# Power.net
KiCad netlist of a schematic drawn in Altium Designer
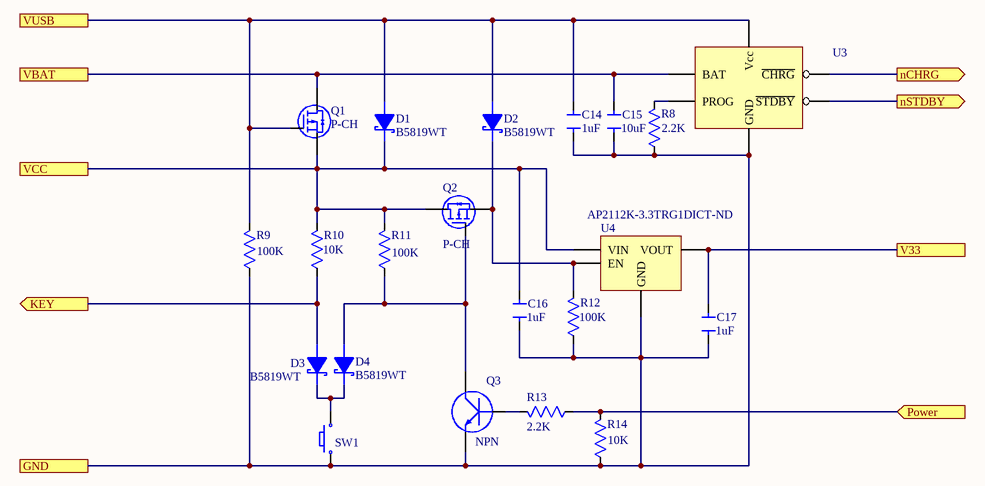
[diagram p0: Power.SchDoc]

(export (version "E")
  (design (tool "Eeschema 10.0.6"))
  (components
    (comp (ref "C14")
      (value "1uF")
      (footprint "CAP_0402")
      (fields (field (name "Comment") "Cap"))
      (libsource (lib "ZGR") (part "Cap"))
    )
    (comp (ref "C15")
      (value "10uF")
      (footprint "Cap_0603")
      (fields (field (name "Comment") "Cap"))
      (libsource (lib "ZGR") (part "Cap"))
    )
    (comp (ref "C16")
      (value "1uF")
      (footprint "CAP_0402")
      (fields (field (name "Comment") "Cap"))
      (libsource (lib "ZGR") (part "Cap"))
    )
    (comp (ref "C17")
      (value "1uF")
      (footprint "CAP_0402")
      (fields (field (name "Comment") "Cap"))
      (libsource (lib "ZGR") (part "Cap"))
    )
    (comp (ref "D1")
      (value "B5819WT")
      (footprint "SOD-523")
      (description "Diode Schottky 40V 1A 2-Pin SOD-523 T/R")
      (fields
        (field (name "MANUFACTURER") "MCC")
        (field (name "MANUFACTURER PART NUMBER") "B5819W-TP")
        (field (name "SUPPLIER PART NUMBER 1") "B5819WT")
      )
      (libsource (lib "ZGR") (part "B5819WT"))
    )
    (comp (ref "D2")
      (value "B5819WT")
      (footprint "SOD-523")
      (description "Diode Schottky 40V 1A 2-Pin SOD-523 T/R")
      (fields
        (field (name "MANUFACTURER") "MCC")
        (field (name "MANUFACTURER PART NUMBER") "B5819W-TP")
        (field (name "SUPPLIER PART NUMBER 1") "B5819WT")
      )
      (libsource (lib "ZGR") (part "B5819WT"))
    )
    (comp (ref "D3")
      (value "B5819WT")
      (footprint "SOD-523")
      (description "Diode Schottky 40V 1A 2-Pin SOD-523 T/R")
      (fields
        (field (name "MANUFACTURER") "MCC")
        (field (name "MANUFACTURER PART NUMBER") "B5819W-TP")
        (field (name "SUPPLIER PART NUMBER 1") "B5819WT")
      )
      (libsource (lib "ZGR") (part "B5819WT"))
    )
    (comp (ref "D4")
      (value "B5819WT")
      (footprint "SOD-523")
      (description "Diode Schottky 40V 1A 2-Pin SOD-523 T/R")
      (fields
        (field (name "MANUFACTURER") "MCC")
        (field (name "MANUFACTURER PART NUMBER") "B5819W-TP")
        (field (name "SUPPLIER PART NUMBER 1") "B5819WT")
      )
      (libsource (lib "ZGR") (part "B5819WT"))
    )
    (comp (ref "Q1")
      (value "SI2301DS-T1")
      (footprint "SOT-23")
      (description "Trans MOSFET P-CH 20V 2.3A 3-Pin TO-236 T/R")
      (fields (field (name "MANUFACTURER") "Vishay Siliconix") (field (name "POLARITY") "P-CH"))
      (libsource (lib "ZGR") (part "SI2301DS-T1"))
    )
    (comp (ref "Q2")
      (value "SI2301DS-T1")
      (footprint "SOT-23")
      (description "Trans MOSFET P-CH 20V 2.3A 3-Pin TO-236 T/R")
      (fields (field (name "MANUFACTURER") "Vishay Siliconix") (field (name "POLARITY") "P-CH"))
      (libsource (lib "ZGR") (part "SI2301DS-T1"))
    )
    (comp (ref "Q3")
      (value "MMS9013L-TP")
      (footprint "SOT-23")
      (description "Trans GP BJT NPN 25V 0.5A 3-Pin SOT-23 T/R")
      (fields (field (name "MANUFACTURER") "MCC") (field (name "POLARITY") "NPN"))
      (libsource (lib "ZGR") (part "MMS9013L-TP"))
    )
    (comp (ref "R8")
      (value "2.2K")
      (footprint "RES_0402")
      (fields (field (name "Comment") "Res"))
      (libsource (lib "ZGR") (part "Res"))
    )
    (comp (ref "R9")
      (value "100K")
      (footprint "RES_0402")
      (fields (field (name "Comment") "Res"))
      (libsource (lib "ZGR") (part "Res"))
    )
    (comp (ref "R10")
      (value "10K")
      (footprint "RES_0402")
      (fields (field (name "Comment") "Res"))
      (libsource (lib "ZGR") (part "Res"))
    )
    (comp (ref "R11")
      (value "100K")
      (footprint "RES_0402")
      (fields (field (name "Comment") "Res"))
      (libsource (lib "ZGR") (part "Res"))
    )
    (comp (ref "R12")
      (value "100K")
      (footprint "RES_0402")
      (fields (field (name "Comment") "Res"))
      (libsource (lib "ZGR") (part "Res"))
    )
    (comp (ref "R13")
      (value "2.2K")
      (footprint "RES_0402")
      (fields (field (name "Comment") "Res"))
      (libsource (lib "ZGR") (part "Res"))
    )
    (comp (ref "R14")
      (value "10K")
      (footprint "RES_0402")
      (fields (field (name "Comment") "Res"))
      (libsource (lib "ZGR") (part "Res"))
    )
    (comp (ref "SW1") (value "SPST") (footprint "ST01-111") (libsource (lib "ZGR") (part "Switch_Button1")))
    (comp (ref "U3")
      (value "TP4059")
      (footprint "SOT23-6")
      (description "600MA SOT23-6")
      (libsource (lib "ZGR") (part "TP4059"))
    )
    (comp (ref "U4")
      (value "AP2112K-3.3TRG1")
      (footprint "SOT23-5")
      (description "IC REG LINEAR 3.3V 600MA SOT23-5")
      (fields
        (field (name "MANUFACTURER") "Diodes")
        (field (name "SUPPLIER PART NUMBER 1") "AP2112K-3.3TRG1DICT-ND")
      )
      (libsource (lib "ZGR") (part "AP2112K-3.3TRG1"))
    )
  )
  (nets
    (net (code "1") (name "/GND") (class "Default")
      (node (ref "C14") (pin "2") (pinfunction "2_2") (pintype "passive"))
      (node (ref "C15") (pin "2") (pinfunction "2_2") (pintype "passive"))
      (node (ref "C16") (pin "2") (pinfunction "2_2") (pintype "passive"))
      (node (ref "C17") (pin "2") (pinfunction "2_2") (pintype "passive"))
      (node (ref "Q3") (pin "3") (pinfunction "3_3") (pintype "passive"))
      (node (ref "R12") (pin "2") (pinfunction "2_2") (pintype "passive"))
      (node (ref "R14") (pin "2") (pinfunction "2_2") (pintype "passive"))
      (node (ref "R8") (pin "2") (pinfunction "2_2") (pintype "passive"))
      (node (ref "R9") (pin "2") (pinfunction "2_2") (pintype "passive"))
      (node (ref "SW1") (pin "2") (pinfunction "2_2") (pintype "passive"))
      (node (ref "U3") (pin "4") (pinfunction "GND_4") (pintype "power_in"))
      (node (ref "U4") (pin "3") (pinfunction "GND_3") (pintype "power_in"))
    )
    (net (code "2") (name "/KEY") (class "Default")
      (node (ref "D3") (pin "1") (pinfunction "1_1") (pintype "passive"))
      (node (ref "R10") (pin "2") (pinfunction "2_2") (pintype "passive"))
    )
    (net (code "3") (name "/Power") (class "Default")
      (node (ref "R13") (pin "2") (pinfunction "2_2") (pintype "passive"))
      (node (ref "R14") (pin "1") (pinfunction "1_1") (pintype "passive"))
    )
    (net (code "4") (name "/V33") (class "Default")
      (node (ref "C17") (pin "1") (pinfunction "1_1") (pintype "passive"))
      (node (ref "U4") (pin "4") (pinfunction "VOUT_4") (pintype "power_in"))
    )
    (net (code "5") (name "/VBAT") (class "Default")
      (node (ref "C15") (pin "1") (pinfunction "1_1") (pintype "passive"))
      (node (ref "Q1") (pin "1") (pinfunction "1_1") (pintype "passive"))
      (node (ref "U3") (pin "6") (pinfunction "BAT_6") (pintype "power_in"))
    )
    (net (code "6") (name "/VCC") (class "Default")
      (node (ref "C16") (pin "1") (pinfunction "1_1") (pintype "passive"))
      (node (ref "D1") (pin "2") (pinfunction "2_2") (pintype "passive"))
      (node (ref "Q1") (pin "3") (pinfunction "3_3") (pintype "passive"))
      (node (ref "Q2") (pin "1") (pinfunction "1_1") (pintype "passive"))
      (node (ref "R10") (pin "1") (pinfunction "1_1") (pintype "passive"))
      (node (ref "R11") (pin "1") (pinfunction "1_1") (pintype "passive"))
      (node (ref "U4") (pin "1") (pinfunction "VIN_1") (pintype "power_in"))
    )
    (net (code "7") (name "/VUSB") (class "Default")
      (node (ref "C14") (pin "1") (pinfunction "1_1") (pintype "passive"))
      (node (ref "D1") (pin "1") (pinfunction "1_1") (pintype "passive"))
      (node (ref "D2") (pin "1") (pinfunction "1_1") (pintype "passive"))
      (node (ref "Q1") (pin "2") (pinfunction "2_2") (pintype "passive"))
      (node (ref "R9") (pin "1") (pinfunction "1_1") (pintype "passive"))
      (node (ref "U3") (pin "1") (pinfunction "Vcc_1") (pintype "power_in"))
    )
    (net (code "8") (name "/nCHRG") (class "Default")
      (node (ref "U3") (pin "2") (pinfunction "CHRG_2") (pintype "passive"))
    )
    (net (code "9") (name "/nSTDBY") (class "Default")
      (node (ref "U3") (pin "3") (pinfunction "STDBY_3") (pintype "open_collector"))
    )
    (net (code "10") (name "Net-(D3-Pad2)") (class "Default")
      (node (ref "D3") (pin "2") (pinfunction "2_2") (pintype "passive"))
      (node (ref "D4") (pin "2") (pinfunction "2_2") (pintype "passive"))
      (node (ref "SW1") (pin "1") (pinfunction "1_1") (pintype "passive"))
    )
    (net (code "11") (name "Net-(D4-Pad1)") (class "Default")
      (node (ref "D4") (pin "1") (pinfunction "1_1") (pintype "passive"))
      (node (ref "Q2") (pin "2") (pinfunction "2_2") (pintype "passive"))
      (node (ref "Q3") (pin "1") (pinfunction "1_1") (pintype "passive"))
      (node (ref "R11") (pin "2") (pinfunction "2_2") (pintype "passive"))
    )
    (net (code "12") (name "Net-(Q3-Pad2)") (class "Default")
      (node (ref "Q3") (pin "2") (pinfunction "2_2") (pintype "passive"))
      (node (ref "R13") (pin "1") (pinfunction "1_1") (pintype "passive"))
    )
    (net (code "13") (name "Net-(U3-PROG)") (class "Default")
      (node (ref "R8") (pin "1") (pinfunction "1_1") (pintype "passive"))
      (node (ref "U3") (pin "5") (pinfunction "PROG_5") (pintype "passive"))
    )
    (net (code "14") (name "Net-(U4-EN)") (class "Default")
      (node (ref "D2") (pin "2") (pinfunction "2_2") (pintype "passive"))
      (node (ref "Q2") (pin "3") (pinfunction "3_3") (pintype "passive"))
      (node (ref "R12") (pin "1") (pinfunction "1_1") (pintype "passive"))
      (node (ref "U4") (pin "2") (pinfunction "EN_2") (pintype "passive"))
    )
  )
)
